# NullerCarrier.net
KiCad netlist of a schematic drawn in Altium Designer
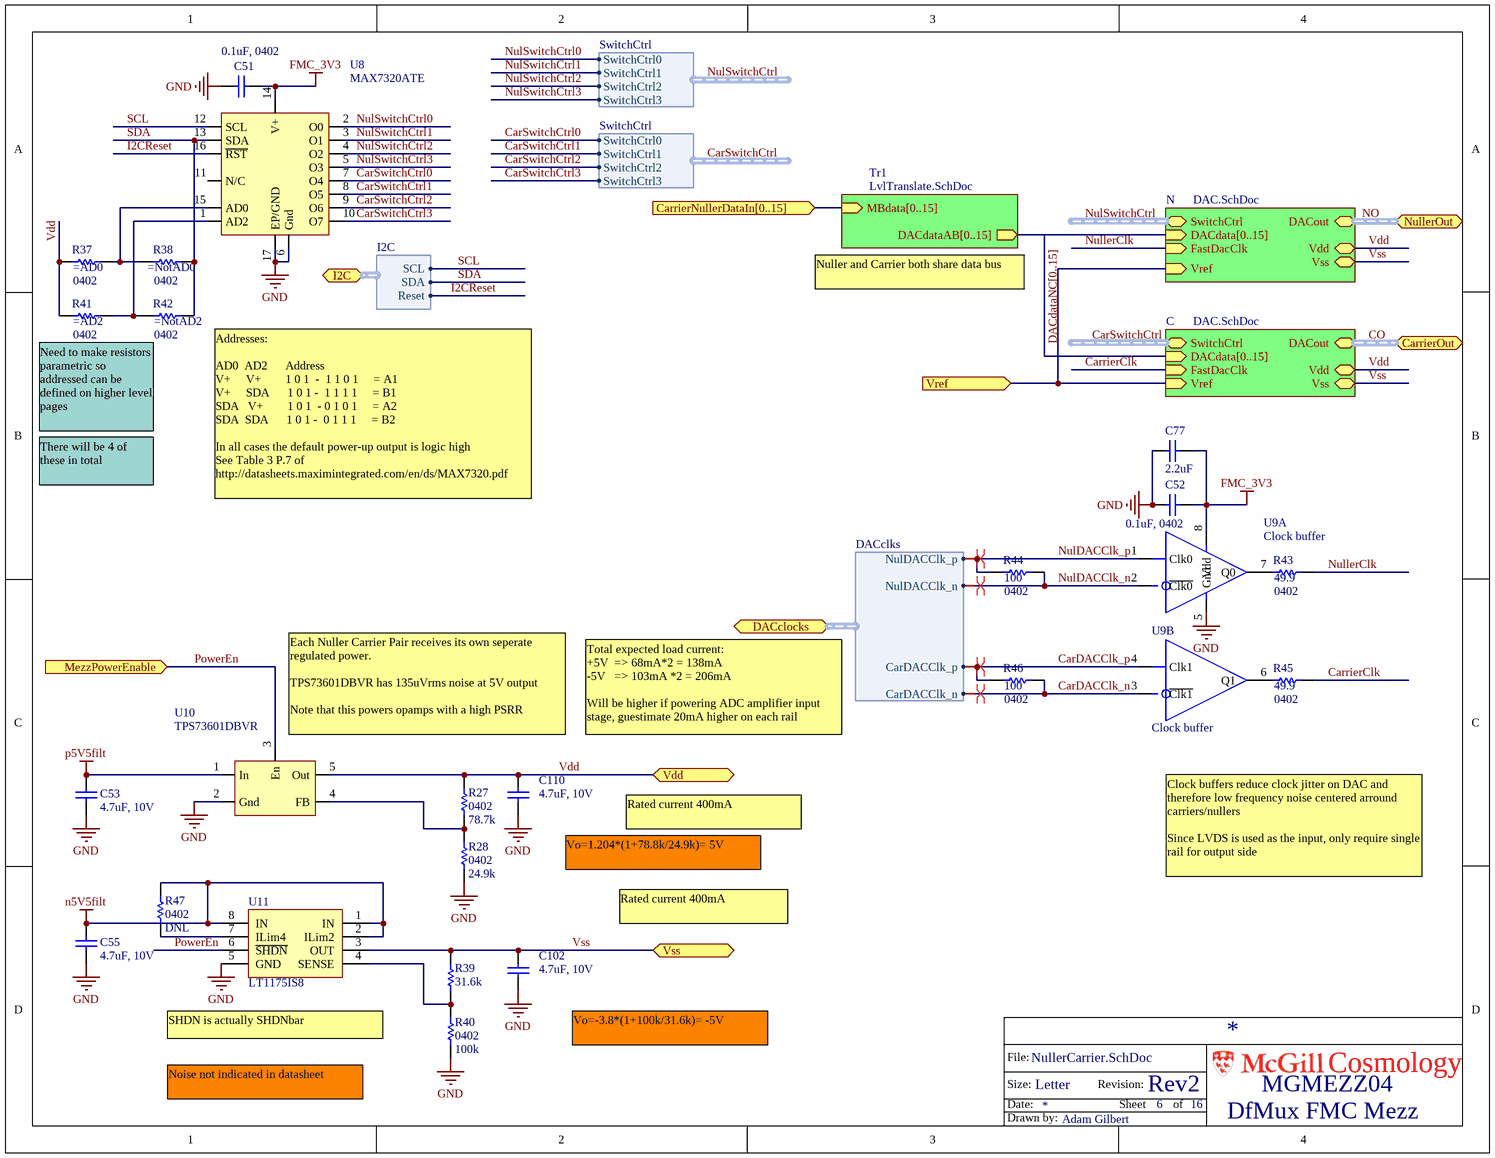
[diagram p0: NullerCarrier.SchDoc]

(export (version "E")
  (design (tool "Eeschema 10.0.6"))
  (components
    (comp (ref "C51")
      (value "0.1uF, 0402")
      (footprint "0402")
      (description "Capacitor, Ceramic, 0402")
      (fields (field (name "MANUFACTURER") "TDK Corporation"))
      (libsource (lib "MGMEZZ04") (part "CAP 0603"))
    )
    (comp (ref "C52")
      (value "0.1uF, 0402")
      (footprint "0402")
      (description "Capacitor, Ceramic, 0402")
      (fields (field (name "MANUFACTURER") "TDK Corporation"))
      (libsource (lib "MGMEZZ04") (part "CAP 0603"))
    )
    (comp (ref "C53")
      (value "4.7uF, 10V")
      (footprint "0805")
      (description "Capacitor, Ceramic, 0805")
      (fields (field (name "MANUFACTURER") "Taiyo Yuden"))
      (libsource (lib "MGMEZZ04") (part "CAP 0805"))
    )
    (comp (ref "C55")
      (value "4.7uF, 10V")
      (footprint "0805")
      (description "Capacitor, Ceramic, 0805")
      (fields (field (name "MANUFACTURER") "Taiyo Yuden"))
      (libsource (lib "MGMEZZ04") (part "CAP 0805"))
    )
    (comp (ref "C77")
      (value "2.2uF")
      (footprint "0603")
      (description "Capacitor, Ceramic, 0603")
      (fields (field (name "MANUFACTURER") "TDK Corporation"))
      (libsource (lib "MGMEZZ04") (part "CAP 0603"))
    )
    (comp (ref "C102")
      (value "4.7uF, 10V")
      (footprint "0805")
      (description "Capacitor, Ceramic, 0805")
      (fields (field (name "MANUFACTURER") "Taiyo Yuden"))
      (libsource (lib "MGMEZZ04") (part "CAP 0805"))
    )
    (comp (ref "C110")
      (value "4.7uF, 10V")
      (footprint "0805")
      (description "Capacitor, Ceramic, 0805")
      (fields (field (name "MANUFACTURER") "Taiyo Yuden"))
      (libsource (lib "MGMEZZ04") (part "CAP 0805"))
    )
    (comp (ref "R27")
      (value "78.7k")
      (footprint "0402")
      (description "Resistor")
      (fields (field (name "MANUFACTURER") "Generic"))
      (libsource (lib "MGMEZZ04") (part "RES 0402"))
    )
    (comp (ref "R28")
      (value "24.9k")
      (footprint "0402")
      (description "Resistor")
      (fields (field (name "MANUFACTURER") "Generic"))
      (libsource (lib "MGMEZZ04") (part "RES 0402"))
    )
    (comp (ref "R37")
      (value "~")
      (footprint "0402")
      (description "Resistor")
      (fields (field (name "MANUFACTURER") "Generic"))
      (libsource (lib "MGMEZZ04") (part "RES 0402"))
    )
    (comp (ref "R38")
      (value "~")
      (footprint "0402")
      (description "Resistor")
      (fields (field (name "MANUFACTURER") "Generic"))
      (libsource (lib "MGMEZZ04") (part "RES 0402"))
    )
    (comp (ref "R39")
      (value "31.6k")
      (footprint "0603")
      (description "Resistor")
      (fields (field (name "MANUFACTURER") "Generic"))
      (libsource (lib "MGMEZZ04") (part "RES 0603"))
    )
    (comp (ref "R40")
      (value "100k")
      (footprint "0402")
      (description "Resistor")
      (fields (field (name "MANUFACTURER") "Generic"))
      (libsource (lib "MGMEZZ04") (part "RES 0402"))
    )
    (comp (ref "R41")
      (value "~")
      (footprint "0402")
      (description "Resistor")
      (fields (field (name "MANUFACTURER") "Generic"))
      (libsource (lib "MGMEZZ04") (part "RES 0402"))
    )
    (comp (ref "R42")
      (value "~")
      (footprint "0402")
      (description "Resistor")
      (fields (field (name "MANUFACTURER") "Generic"))
      (libsource (lib "MGMEZZ04") (part "RES 0402"))
    )
    (comp (ref "R43")
      (value "49.9")
      (footprint "0402")
      (description "Resistor")
      (fields (field (name "MANUFACTURER") "Generic"))
      (libsource (lib "MGMEZZ04") (part "RES 0402"))
    )
    (comp (ref "R44")
      (value "100")
      (footprint "0402")
      (description "Resistor")
      (fields (field (name "MANUFACTURER") "Generic"))
      (libsource (lib "MGMEZZ04") (part "RES 0402"))
    )
    (comp (ref "R45")
      (value "49.9")
      (footprint "0402")
      (description "Resistor")
      (fields (field (name "MANUFACTURER") "Generic"))
      (libsource (lib "MGMEZZ04") (part "RES 0402"))
    )
    (comp (ref "R46")
      (value "100")
      (footprint "0402")
      (description "Resistor")
      (fields (field (name "MANUFACTURER") "Generic"))
      (libsource (lib "MGMEZZ04") (part "RES 0402"))
    )
    (comp (ref "R47")
      (value "DNL")
      (footprint "0402")
      (description "Resistor")
      (fields (field (name "MANUFACTURER") "Generic"))
      (libsource (lib "MGMEZZ04") (part "RES 0402"))
    )
    (comp (ref "U8")
      (value "MAX7320ATE")
      (footprint "QFN127P600-8N-MAX7319")
      (description "IO expander 8bit I2C")
      (fields (field (name "MANUFACTURER") "Maxim Integrated"))
      (libsource (lib "MGMEZZ04") (part "MAX7320ATE"))
    )
    (comp (ref "U9")
      (value "Clock buffer")
      (footprint "SO8")
      (description "IC CLK TRANSLTR 1:1 350MHZ 8SOIC")
      (fields (field (name "MANUFACTURER") "IDT, Integrated Device Technology Inc"))
      (libsource (lib "MGMEZZ04") (part "ICS83023AMILF"))
    )
    (comp (ref "U10")
      (value "TPS73601DBVR")
      (footprint "SOT23-5")
      (description "Adjustable 30uVrms noise 400mA regulator")
      (fields (field (name "MANUFACTURER") "Texas Instruments"))
      (libsource (lib "MGMEZZ04") (part "TPS73601DBVR"))
    )
    (comp (ref "U11")
      (value "LT1175IS8")
      (footprint "SO8")
      (description "REG, negative micropower low dropout")
      (fields (field (name "MANUFACTURER") "Linear Technology"))
      (libsource (lib "MGMEZZ04") (part "LT1175IS8"))
    )
  )
  (nets
    (net (code "41") (name "/CarDACClk_n") (class "Default")
      (node (ref "R46") (pin "2") (pinfunction "2_2") (pintype "passive"))
      (node (ref "U9") (pin "3") (pinfunction "~{Clk1}_3") (pintype "passive"))
    )
    (net (code "42") (name "/CarDACClk_p") (class "Default")
      (node (ref "R46") (pin "1") (pinfunction "1_1") (pintype "passive"))
      (node (ref "U9") (pin "4") (pinfunction "Clk1_4") (pintype "passive"))
    )
    (net (code "43") (name "/CarSwitchCtrl0") (class "Default")
      (node (ref "U8") (pin "7") (pinfunction "O4_7") (pintype "passive"))
    )
    (net (code "44") (name "/CarSwitchCtrl1") (class "Default")
      (node (ref "U8") (pin "8") (pinfunction "O5_8") (pintype "passive"))
    )
    (net (code "45") (name "/CarSwitchCtrl2") (class "Default")
      (node (ref "U8") (pin "9") (pinfunction "O6_9") (pintype "passive"))
    )
    (net (code "46") (name "/CarSwitchCtrl3") (class "Default")
      (node (ref "U8") (pin "10") (pinfunction "O7_10") (pintype "passive"))
    )
    (net (code "48") (name "/CarrierClk") (class "Default")
      (node (ref "R45") (pin "2") (pinfunction "2_2") (pintype "passive"))
    )
    (net (code "52") (name "/I2CReset") (class "Default")
      (node (ref "U8") (pin "16") (pinfunction "~{RST}_16") (pintype "passive"))
    )
    (net (code "53") (name "/NulDACClk_n") (class "Default")
      (node (ref "R44") (pin "2") (pinfunction "2_2") (pintype "passive"))
      (node (ref "U9") (pin "2") (pinfunction "~{Clk0}_2") (pintype "passive"))
    )
    (net (code "54") (name "/NulDACClk_p") (class "Default")
      (node (ref "R44") (pin "1") (pinfunction "1_1") (pintype "passive"))
      (node (ref "U9") (pin "1") (pinfunction "Clk0_1") (pintype "passive"))
    )
    (net (code "55") (name "/NulSwitchCtrl0") (class "Default")
      (node (ref "U8") (pin "2") (pinfunction "O0_2") (pintype "passive"))
    )
    (net (code "56") (name "/NulSwitchCtrl1") (class "Default")
      (node (ref "U8") (pin "3") (pinfunction "O1_3") (pintype "passive"))
    )
    (net (code "57") (name "/NulSwitchCtrl2") (class "Default")
      (node (ref "U8") (pin "4") (pinfunction "O2_4") (pintype "passive"))
    )
    (net (code "58") (name "/NulSwitchCtrl3") (class "Default")
      (node (ref "U8") (pin "5") (pinfunction "O3_5") (pintype "passive"))
    )
    (net (code "60") (name "/NullerClk") (class "Default")
      (node (ref "R43") (pin "2") (pinfunction "2_2") (pintype "passive"))
    )
    (net (code "61") (name "/PowerEn") (class "Default")
      (node (ref "U10") (pin "3") (pinfunction "En_3") (pintype "passive"))
      (node (ref "U11") (pin "6") (pinfunction "SHDN_6") (pintype "passive"))
    )
    (net (code "62") (name "/SCL") (class "Default")
      (node (ref "U8") (pin "12") (pinfunction "SCL_12") (pintype "passive"))
    )
    (net (code "63") (name "/SDA") (class "Default")
      (node (ref "R38") (pin "2") (pinfunction "2_2") (pintype "passive"))
      (node (ref "R42") (pin "2") (pinfunction "2_2") (pintype "passive"))
      (node (ref "U8") (pin "13") (pinfunction "SDA_13") (pintype "passive"))
    )
    (net (code "64") (name "/Vdd") (class "Default")
      (node (ref "C110") (pin "2") (pinfunction "2_2") (pintype "passive"))
      (node (ref "R27") (pin "2") (pinfunction "2_2") (pintype "passive"))
      (node (ref "R37") (pin "1") (pinfunction "1_1") (pintype "passive"))
      (node (ref "R41") (pin "1") (pinfunction "1_1") (pintype "passive"))
      (node (ref "U10") (pin "5") (pinfunction "Out_5") (pintype "passive"))
    )
    (net (code "66") (name "/Vss") (class "Default")
      (node (ref "C102") (pin "2") (pinfunction "2_2") (pintype "passive"))
      (node (ref "R39") (pin "1") (pinfunction "1_1") (pintype "passive"))
      (node (ref "U11") (pin "3") (pinfunction "OUT_3") (pintype "passive"))
    )
    (net (code "73") (name "FMC_3V3") (class "Default")
      (node (ref "C51") (pin "2") (pinfunction "2_2") (pintype "passive"))
      (node (ref "C52") (pin "1") (pinfunction "1_1") (pintype "passive"))
      (node (ref "C77") (pin "2") (pinfunction "2_2") (pintype "passive"))
      (node (ref "U8") (pin "14") (pinfunction "V+_14") (pintype "passive"))
      (node (ref "U9") (pin "8") (pinfunction "Vdd_8") (pintype "passive"))
    )
    (net (code "74") (name "GND") (class "Default")
      (node (ref "C102") (pin "1") (pinfunction "1_1") (pintype "passive"))
      (node (ref "C110") (pin "1") (pinfunction "1_1") (pintype "passive"))
      (node (ref "C51") (pin "1") (pinfunction "1_1") (pintype "passive"))
      (node (ref "C52") (pin "2") (pinfunction "2_2") (pintype "passive"))
      (node (ref "C53") (pin "1") (pinfunction "1_1") (pintype "passive"))
      (node (ref "C55") (pin "1") (pinfunction "1_1") (pintype "passive"))
      (node (ref "C77") (pin "1") (pinfunction "1_1") (pintype "passive"))
      (node (ref "R28") (pin "1") (pinfunction "1_1") (pintype "passive"))
      (node (ref "R40") (pin "1") (pinfunction "1_1") (pintype "passive"))
      (node (ref "U10") (pin "2") (pinfunction "Gnd_2") (pintype "passive"))
      (node (ref "U11") (pin "5") (pinfunction "GND_5") (pintype "passive"))
      (node (ref "U8") (pin "17") (pinfunction "EP/GND_17") (pintype "passive"))
      (node (ref "U8") (pin "6") (pinfunction "Gnd_6") (pintype "passive"))
      (node (ref "U9") (pin "5") (pinfunction "Gnd_5") (pintype "passive"))
    )
    (net (code "75") (name "Net-(U8-AD0)") (class "Default")
      (node (ref "R37") (pin "2") (pinfunction "2_2") (pintype "passive"))
      (node (ref "R38") (pin "1") (pinfunction "1_1") (pintype "passive"))
      (node (ref "U8") (pin "15") (pinfunction "AD0_15") (pintype "passive"))
    )
    (net (code "76") (name "Net-(U8-AD2)") (class "Default")
      (node (ref "R41") (pin "2") (pinfunction "2_2") (pintype "passive"))
      (node (ref "R42") (pin "1") (pinfunction "1_1") (pintype "passive"))
      (node (ref "U8") (pin "1") (pinfunction "AD2_1") (pintype "passive"))
    )
    (net (code "77") (name "Net-(U9A-Q0)") (class "Default")
      (node (ref "R43") (pin "1") (pinfunction "1_1") (pintype "passive"))
      (node (ref "U9") (pin "7") (pinfunction "Q0_7") (pintype "passive"))
    )
    (net (code "78") (name "Net-(U9B-Q1)") (class "Default")
      (node (ref "R45") (pin "1") (pinfunction "1_1") (pintype "passive"))
      (node (ref "U9") (pin "6") (pinfunction "Q1_6") (pintype "passive"))
    )
    (net (code "79") (name "Net-(U10-FB)") (class "Default")
      (node (ref "R27") (pin "1") (pinfunction "1_1") (pintype "passive"))
      (node (ref "R28") (pin "2") (pinfunction "2_2") (pintype "passive"))
      (node (ref "U10") (pin "4") (pinfunction "FB_4") (pintype "passive"))
    )
    (net (code "80") (name "Net-(U11-ILim4)") (class "Default")
      (node (ref "R47") (pin "1") (pinfunction "1_1") (pintype "passive"))
      (node (ref "U11") (pin "7") (pinfunction "ILim4_7") (pintype "passive"))
    )
    (net (code "81") (name "Net-(U11-SENSE)") (class "Default")
      (node (ref "R39") (pin "2") (pinfunction "2_2") (pintype "passive"))
      (node (ref "R40") (pin "2") (pinfunction "2_2") (pintype "passive"))
      (node (ref "U11") (pin "4") (pinfunction "SENSE_4") (pintype "power_in"))
    )
    (net (code "82") (name "n5V5filt") (class "Default")
      (node (ref "C55") (pin "2") (pinfunction "2_2") (pintype "passive"))
      (node (ref "R47") (pin "2") (pinfunction "2_2") (pintype "passive"))
      (node (ref "U11") (pin "1") (pinfunction "IN_1") (pintype "power_in"))
      (node (ref "U11") (pin "2") (pinfunction "ILim2_2") (pintype "passive"))
      (node (ref "U11") (pin "8") (pinfunction "IN_8") (pintype "power_in"))
    )
    (net (code "83") (name "p5V5filt") (class "Default")
      (node (ref "C53") (pin "2") (pinfunction "2_2") (pintype "passive"))
      (node (ref "U10") (pin "1") (pinfunction "In_1") (pintype "passive"))
    )
    (net (code "84") (name "unconnected-(U8-N{slash}C-Pad11)") (class "Default")
      (node (ref "U8") (pin "11") (pinfunction "N/C_11") (pintype "passive"))
    )
  )
)
